# P12_CAN_FD1_4.net
KiCad netlist of a schematic drawn in Altium Designer
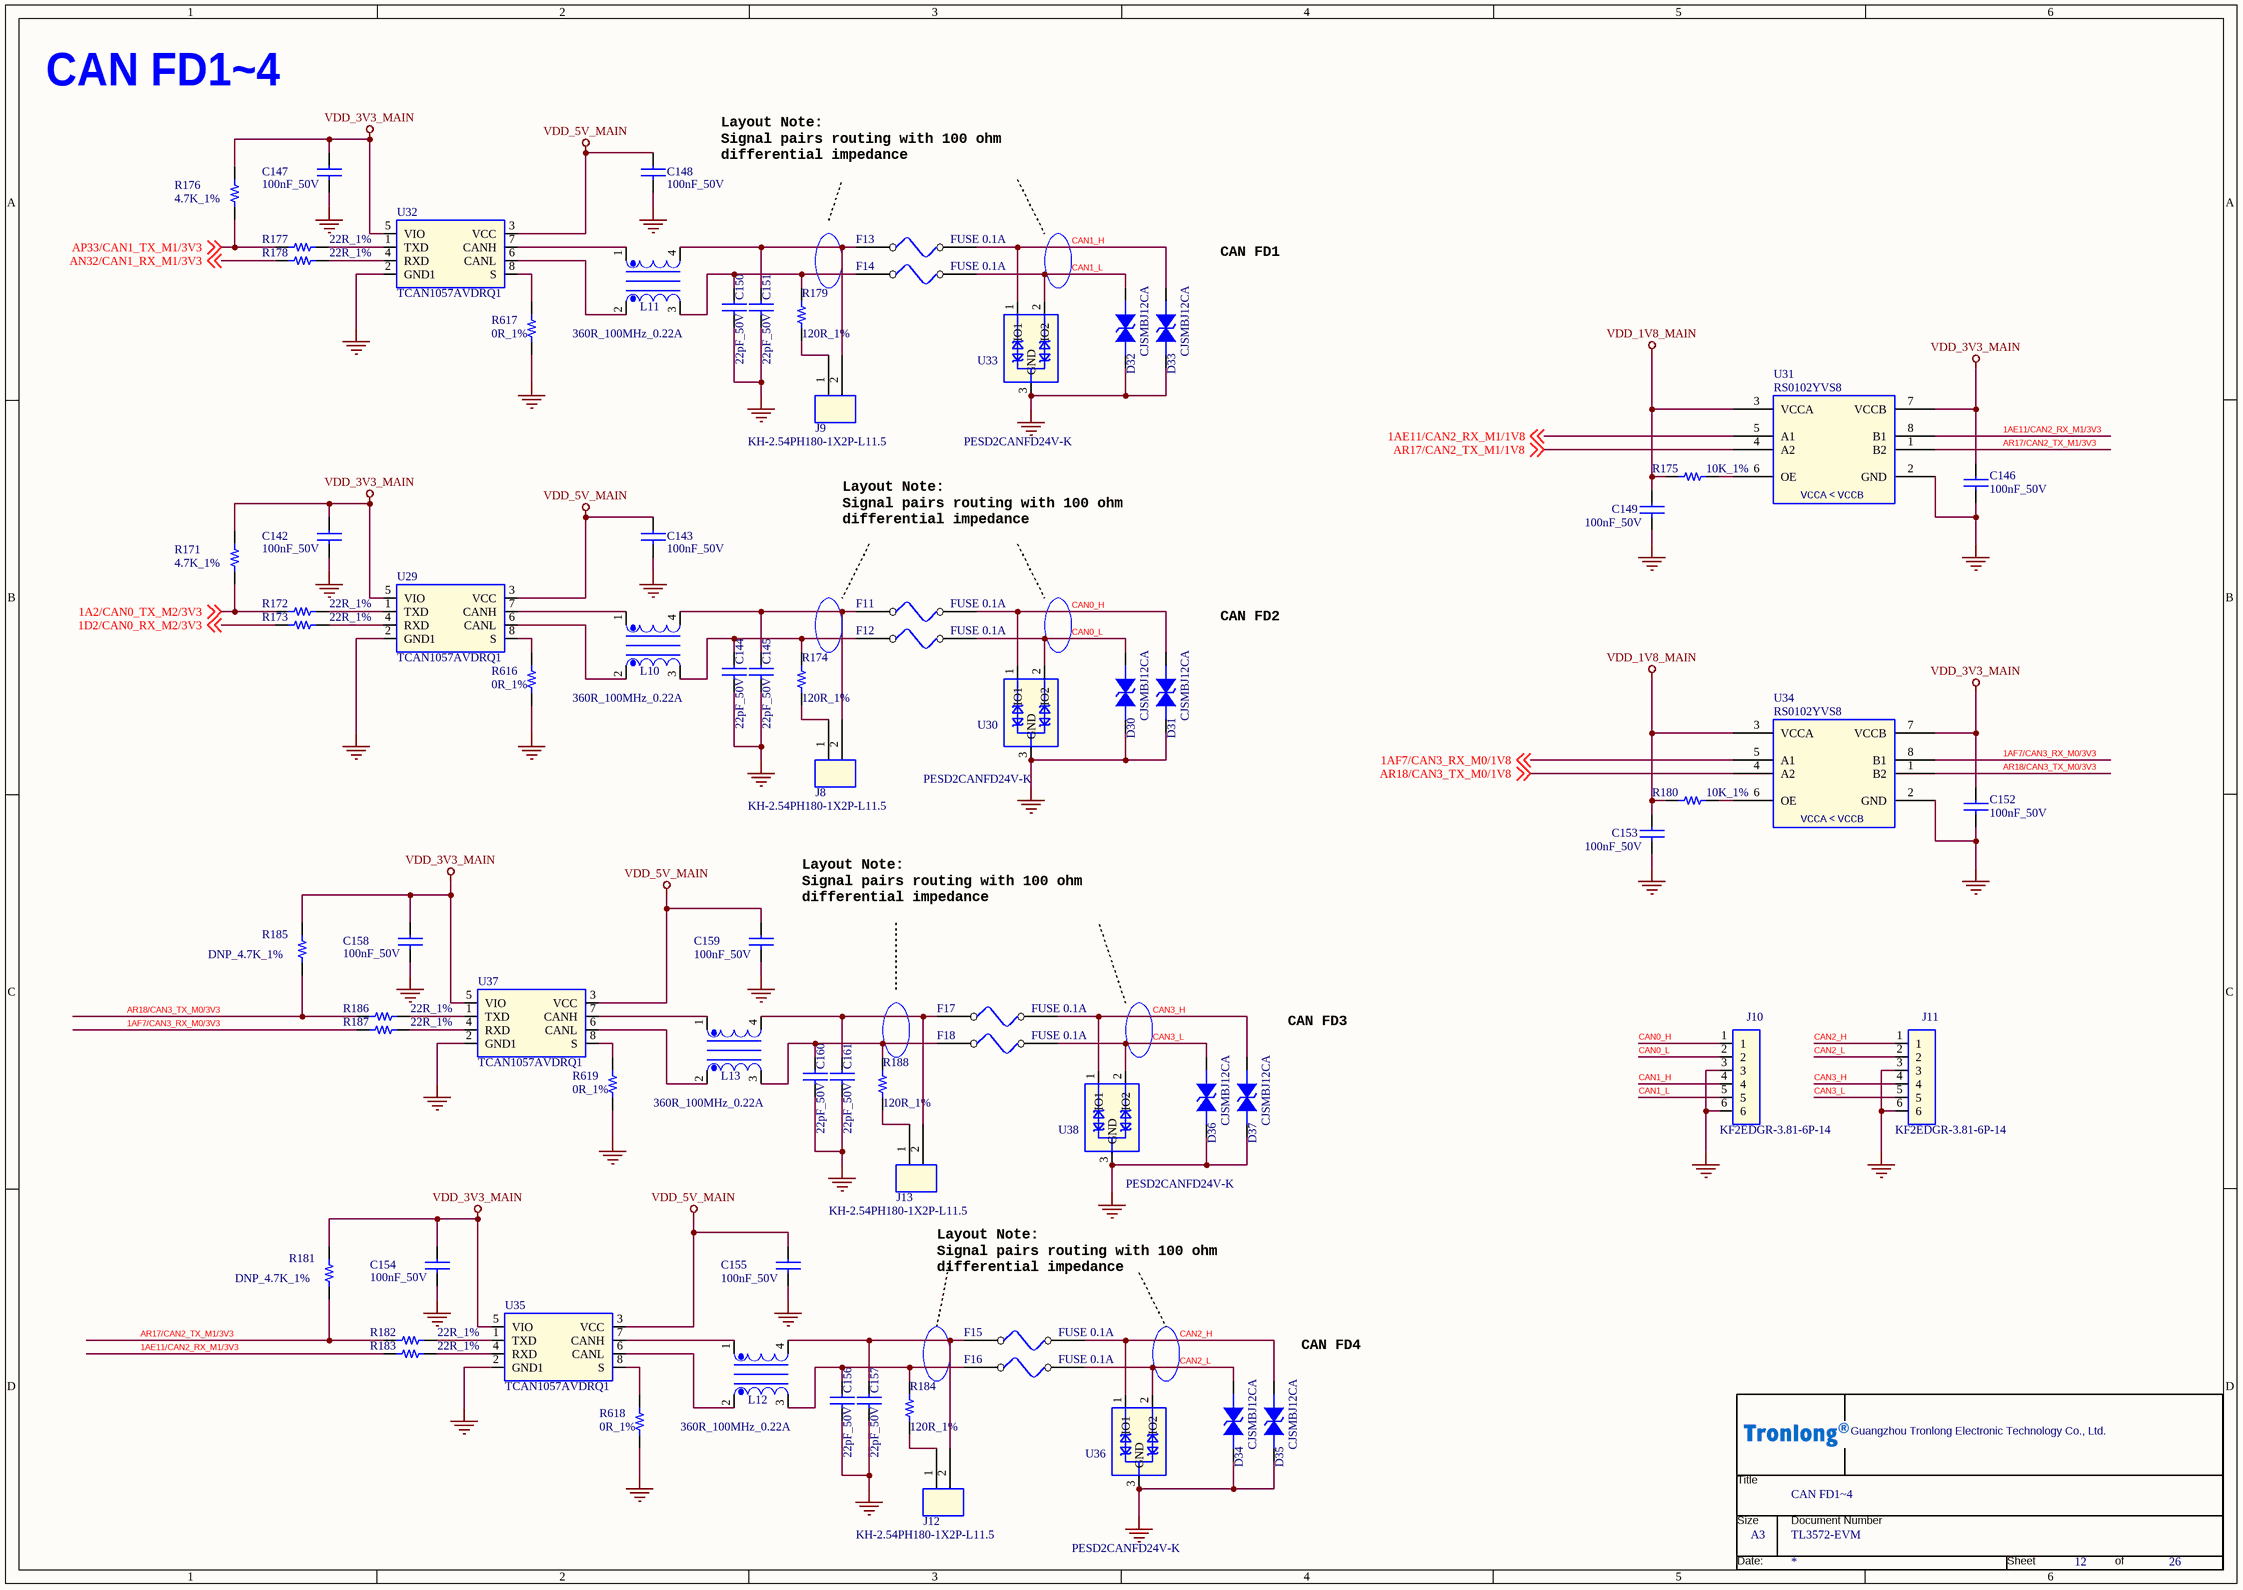
[diagram p0: P12_CAN FD1~4.SchDoc]

(export (version "E")
  (design (tool "Eeschema 10.0.6"))
  (components
    (comp (ref "*")
      (value "Tronlong_TITTLE_20211115")
      (fields
        (field (name "DOC") "TL3572-EVM")
        (field (name "TITLE") "CAN FD1~4")
        (field (name "ORGNAME") "Guangzhou Tronlong Electronic Technology Co., Ltd.")
        (field (name "PAGE SIZE") "A3")
        (field (name "PAGE NUMBER") "12")
        (field (name "PAGE COUNT") "26")
      )
      (libsource (lib "*") (part "Tronlong_TITTLE_20211115"))
    )
    (comp (ref "C142")
      (value "100nF_50V")
      (footprint "C0402")
      (description "贴片陶瓷电容,100nF,10%,50V,X7R")
      (fields
        (field (name "MANUFACTURER") "广东风华高新科技股份有限公司（FH）")
        (field (name "MANUFACTURER PARTNUMBER") "0402B104K500NT")
      )
      (libsource (lib "*") (part "CAP NP_Dup2"))
    )
    (comp (ref "C143")
      (value "100nF_50V")
      (footprint "C0402")
      (description "贴片陶瓷电容,100nF,10%,50V,X7R")
      (fields
        (field (name "MANUFACTURER") "广东风华高新科技股份有限公司（FH）")
        (field (name "MANUFACTURER PARTNUMBER") "0402B104K500NT")
      )
      (libsource (lib "*") (part "CAP NP_Dup2"))
    )
    (comp (ref "C144")
      (value "22pF_50V")
      (footprint "C0603")
      (description "贴片陶瓷电容,22pF,5%,50V,COG")
      (fields
        (field (name "MANUFACTURER PARTNUMBER") "0603CG220J500NT")
        (field (name "MANUFACTURER") "广东风华高新科技股份有限公司（FH）")
      )
      (libsource (lib "*") (part "CAP NP_Dup2"))
    )
    (comp (ref "C145")
      (value "22pF_50V")
      (footprint "C0603")
      (description "贴片陶瓷电容,22pF,5%,50V,COG")
      (fields
        (field (name "MANUFACTURER PARTNUMBER") "0603CG220J500NT")
        (field (name "MANUFACTURER") "广东风华高新科技股份有限公司（FH）")
      )
      (libsource (lib "*") (part "CAP NP_Dup2"))
    )
    (comp (ref "C146")
      (value "100nF_50V")
      (footprint "C0402")
      (description "贴片陶瓷电容,100nF,10%,50V,X7R")
      (fields
        (field (name "MANUFACTURER") "广东风华高新科技股份有限公司（FH）")
        (field (name "MANUFACTURER PARTNUMBER") "0402B104K500NT")
      )
      (libsource (lib "*") (part "CAP NP_Dup3"))
    )
    (comp (ref "C147")
      (value "100nF_50V")
      (footprint "C0402")
      (description "贴片陶瓷电容,100nF,10%,50V,X7R")
      (fields
        (field (name "MANUFACTURER PARTNUMBER") "0402B104K500NT")
        (field (name "MANUFACTURER") "广东风华高新科技股份有限公司（FH）")
      )
      (libsource (lib "*") (part "CAP NP_Dup2"))
    )
    (comp (ref "C148")
      (value "100nF_50V")
      (footprint "C0402")
      (description "贴片陶瓷电容,100nF,10%,50V,X7R")
      (fields
        (field (name "MANUFACTURER PARTNUMBER") "0402B104K500NT")
        (field (name "MANUFACTURER") "广东风华高新科技股份有限公司（FH）")
      )
      (libsource (lib "*") (part "CAP NP_Dup2"))
    )
    (comp (ref "C149")
      (value "100nF_50V")
      (footprint "C0402")
      (description "贴片陶瓷电容,100nF,10%,50V,X7R")
      (fields
        (field (name "MANUFACTURER") "广东风华高新科技股份有限公司（FH）")
        (field (name "MANUFACTURER PARTNUMBER") "0402B104K500NT")
      )
      (libsource (lib "*") (part "CAP NP_Dup3"))
    )
    (comp (ref "C150")
      (value "22pF_50V")
      (footprint "C0603")
      (description "贴片陶瓷电容,22pF,5%,50V,COG")
      (fields
        (field (name "MANUFACTURER PARTNUMBER") "0603CG220J500NT")
        (field (name "MANUFACTURER") "广东风华高新科技股份有限公司（FH）")
      )
      (libsource (lib "*") (part "CAP NP_Dup2"))
    )
    (comp (ref "C151")
      (value "22pF_50V")
      (footprint "C0603")
      (description "贴片陶瓷电容,22pF,5%,50V,COG")
      (fields
        (field (name "MANUFACTURER") "广东风华高新科技股份有限公司（FH）")
        (field (name "MANUFACTURER PARTNUMBER") "0603CG220J500NT")
      )
      (libsource (lib "*") (part "CAP NP_Dup2"))
    )
    (comp (ref "C152")
      (value "100nF_50V")
      (footprint "C0402")
      (description "贴片陶瓷电容,100nF,10%,50V,X7R")
      (fields
        (field (name "MANUFACTURER") "广东风华高新科技股份有限公司（FH）")
        (field (name "MANUFACTURER PARTNUMBER") "0402B104K500NT")
      )
      (libsource (lib "*") (part "CAP NP_Dup3"))
    )
    (comp (ref "C153")
      (value "100nF_50V")
      (footprint "C0402")
      (description "贴片陶瓷电容,100nF,10%,50V,X7R")
      (fields
        (field (name "MANUFACTURER") "广东风华高新科技股份有限公司（FH）")
        (field (name "MANUFACTURER PARTNUMBER") "0402B104K500NT")
      )
      (libsource (lib "*") (part "CAP NP_Dup3"))
    )
    (comp (ref "C154")
      (value "100nF_50V")
      (footprint "C0402")
      (description "贴片陶瓷电容,100nF,10%,50V,X7R")
      (fields
        (field (name "MANUFACTURER") "广东风华高新科技股份有限公司（FH）")
        (field (name "MANUFACTURER PARTNUMBER") "0402B104K500NT")
      )
      (libsource (lib "*") (part "CAP NP_Dup2"))
    )
    (comp (ref "C155")
      (value "100nF_50V")
      (footprint "C0402")
      (description "贴片陶瓷电容,100nF,10%,50V,X7R")
      (fields
        (field (name "MANUFACTURER") "广东风华高新科技股份有限公司（FH）")
        (field (name "MANUFACTURER PARTNUMBER") "0402B104K500NT")
      )
      (libsource (lib "*") (part "CAP NP_Dup2"))
    )
    (comp (ref "C156")
      (value "22pF_50V")
      (footprint "C0603")
      (description "贴片陶瓷电容,22pF,5%,50V,COG")
      (fields
        (field (name "MANUFACTURER PARTNUMBER") "0603CG220J500NT")
        (field (name "MANUFACTURER") "广东风华高新科技股份有限公司（FH）")
      )
      (libsource (lib "*") (part "CAP NP_Dup2"))
    )
    (comp (ref "C157")
      (value "22pF_50V")
      (footprint "C0603")
      (description "贴片陶瓷电容,22pF,5%,50V,COG")
      (fields
        (field (name "MANUFACTURER PARTNUMBER") "0603CG220J500NT")
        (field (name "MANUFACTURER") "广东风华高新科技股份有限公司（FH）")
      )
      (libsource (lib "*") (part "CAP NP_Dup2"))
    )
    (comp (ref "C158")
      (value "100nF_50V")
      (footprint "C0402")
      (description "贴片陶瓷电容,100nF,10%,50V,X7R")
      (fields
        (field (name "MANUFACTURER") "广东风华高新科技股份有限公司（FH）")
        (field (name "MANUFACTURER PARTNUMBER") "0402B104K500NT")
      )
      (libsource (lib "*") (part "CAP NP_Dup2"))
    )
    (comp (ref "C159")
      (value "100nF_50V")
      (footprint "C0402")
      (description "贴片陶瓷电容,100nF,10%,50V,X7R")
      (fields
        (field (name "MANUFACTURER PARTNUMBER") "0402B104K500NT")
        (field (name "MANUFACTURER") "广东风华高新科技股份有限公司（FH）")
      )
      (libsource (lib "*") (part "CAP NP_Dup2"))
    )
    (comp (ref "C160")
      (value "22pF_50V")
      (footprint "C0603")
      (description "贴片陶瓷电容,22pF,5%,50V,COG")
      (fields
        (field (name "MANUFACTURER") "广东风华高新科技股份有限公司（FH）")
        (field (name "MANUFACTURER PARTNUMBER") "0603CG220J500NT")
      )
      (libsource (lib "*") (part "CAP NP_Dup2"))
    )
    (comp (ref "C161")
      (value "22pF_50V")
      (footprint "C0603")
      (description "贴片陶瓷电容,22pF,5%,50V,COG")
      (fields
        (field (name "MANUFACTURER") "广东风华高新科技股份有限公司（FH）")
        (field (name "MANUFACTURER PARTNUMBER") "0603CG220J500NT")
      )
      (libsource (lib "*") (part "CAP NP_Dup2"))
    )
    (comp (ref "D30")
      (value "CJSMBJ12CA")
      (footprint "SMB")
      (description "TVS二极管,VRWM=12V,VBR=13.35V,一组,双向")
      (fields (field (name "MANUFACTURER") "江苏长晶科技股份有限公司（JSCJ）"))
      (libsource (lib "*") (part "DIODE-TRIG"))
    )
    (comp (ref "D31")
      (value "CJSMBJ12CA")
      (footprint "SMB")
      (description "TVS二极管,VRWM=12V,VBR=13.35V,一组,双向")
      (fields (field (name "MANUFACTURER") "江苏长晶科技股份有限公司（JSCJ）"))
      (libsource (lib "*") (part "DIODE-TRIG"))
    )
    (comp (ref "D32")
      (value "CJSMBJ12CA")
      (footprint "SMB")
      (description "TVS二极管,VRWM=12V,VBR=13.35V,一组,双向")
      (fields (field (name "MANUFACTURER") "江苏长晶科技股份有限公司（JSCJ）"))
      (libsource (lib "*") (part "DIODE-TRIG"))
    )
    (comp (ref "D33")
      (value "CJSMBJ12CA")
      (footprint "SMB")
      (description "TVS二极管,VRWM=12V,VBR=13.35V,一组,双向")
      (fields (field (name "MANUFACTURER") "江苏长晶科技股份有限公司（JSCJ）"))
      (libsource (lib "*") (part "DIODE-TRIG"))
    )
    (comp (ref "D34")
      (value "CJSMBJ12CA")
      (footprint "SMB")
      (description "TVS二极管,VRWM=12V,VBR=13.35V,一组,双向")
      (fields (field (name "MANUFACTURER") "江苏长晶科技股份有限公司（JSCJ）"))
      (libsource (lib "*") (part "DIODE-TRIG"))
    )
    (comp (ref "D35")
      (value "CJSMBJ12CA")
      (footprint "SMB")
      (description "TVS二极管,VRWM=12V,VBR=13.35V,一组,双向")
      (fields (field (name "MANUFACTURER") "江苏长晶科技股份有限公司（JSCJ）"))
      (libsource (lib "*") (part "DIODE-TRIG"))
    )
    (comp (ref "D36")
      (value "CJSMBJ12CA")
      (footprint "SMB")
      (description "TVS二极管,VRWM=12V,VBR=13.35V,一组,双向")
      (fields (field (name "MANUFACTURER") "江苏长晶科技股份有限公司（JSCJ）"))
      (libsource (lib "*") (part "DIODE-TRIG"))
    )
    (comp (ref "D37")
      (value "CJSMBJ12CA")
      (footprint "SMB")
      (description "TVS二极管,VRWM=12V,VBR=13.35V,一组,双向")
      (fields (field (name "MANUFACTURER") "江苏长晶科技股份有限公司（JSCJ）"))
      (libsource (lib "*") (part "DIODE-TRIG"))
    )
    (comp (ref "F11")
      (value "FUSE 0.1A")
      (footprint "F0805")
      (description "自恢复保险丝,Vmax=24V,Imax=100A,Ihold=0.1A")
      (fields
        (field (name "MANUFACTURER") "东莞市竞沃电子科技有限公司（TLC）")
        (field (name "MANUFACTURER PARTNUMBER") "TLC-PSMD010/24")
      )
      (libsource (lib "*") (part "FUSE"))
    )
    (comp (ref "F12")
      (value "FUSE 0.1A")
      (footprint "F0805")
      (description "自恢复保险丝,Vmax=24V,Imax=100A,Ihold=0.1A")
      (fields
        (field (name "MANUFACTURER PARTNUMBER") "TLC-PSMD010/24")
        (field (name "MANUFACTURER") "东莞市竞沃电子科技有限公司（TLC）")
      )
      (libsource (lib "*") (part "FUSE"))
    )
    (comp (ref "F13")
      (value "FUSE 0.1A")
      (footprint "F0805")
      (description "自恢复保险丝,Vmax=24V,Imax=100A,Ihold=0.1A")
      (fields
        (field (name "MANUFACTURER") "东莞市竞沃电子科技有限公司（TLC）")
        (field (name "MANUFACTURER PARTNUMBER") "TLC-PSMD010/24")
      )
      (libsource (lib "*") (part "FUSE"))
    )
    (comp (ref "F14")
      (value "FUSE 0.1A")
      (footprint "F0805")
      (description "自恢复保险丝,Vmax=24V,Imax=100A,Ihold=0.1A")
      (fields
        (field (name "MANUFACTURER PARTNUMBER") "TLC-PSMD010/24")
        (field (name "MANUFACTURER") "东莞市竞沃电子科技有限公司（TLC）")
      )
      (libsource (lib "*") (part "FUSE"))
    )
    (comp (ref "F15")
      (value "FUSE 0.1A")
      (footprint "F0805")
      (description "自恢复保险丝,Vmax=24V,Imax=100A,Ihold=0.1A")
      (fields
        (field (name "MANUFACTURER") "东莞市竞沃电子科技有限公司（TLC）")
        (field (name "MANUFACTURER PARTNUMBER") "TLC-PSMD010/24")
      )
      (libsource (lib "*") (part "FUSE"))
    )
    (comp (ref "F16")
      (value "FUSE 0.1A")
      (footprint "F0805")
      (description "自恢复保险丝,Vmax=24V,Imax=100A,Ihold=0.1A")
      (fields
        (field (name "MANUFACTURER PARTNUMBER") "TLC-PSMD010/24")
        (field (name "MANUFACTURER") "东莞市竞沃电子科技有限公司（TLC）")
      )
      (libsource (lib "*") (part "FUSE"))
    )
    (comp (ref "F17")
      (value "FUSE 0.1A")
      (footprint "F0805")
      (description "自恢复保险丝,Vmax=24V,Imax=100A,Ihold=0.1A")
      (fields
        (field (name "MANUFACTURER PARTNUMBER") "TLC-PSMD010/24")
        (field (name "MANUFACTURER") "东莞市竞沃电子科技有限公司（TLC）")
      )
      (libsource (lib "*") (part "FUSE"))
    )
    (comp (ref "F18")
      (value "FUSE 0.1A")
      (footprint "F0805")
      (description "自恢复保险丝,Vmax=24V,Imax=100A,Ihold=0.1A")
      (fields
        (field (name "MANUFACTURER") "东莞市竞沃电子科技有限公司（TLC）")
        (field (name "MANUFACTURER PARTNUMBER") "TLC-PSMD010/24")
      )
      (libsource (lib "*") (part "FUSE"))
    )
    (comp (ref "J8")
      (value "KH-2.54PH180-1X2P-L11.5")
      (footprint "header_1x2p_2d54_male")
      (description "插件单排排针,1x2P,2.54mm,180度")
      (fields (field (name "MANUFACTURER") "深圳市金航标电子有限公司(kinghelm)"))
      (libsource (lib "*") (part "CON2_0"))
    )
    (comp (ref "J9")
      (value "KH-2.54PH180-1X2P-L11.5")
      (footprint "header_1x2p_2d54_male")
      (description "插件单排排针,1x2P,2.54mm,180度")
      (fields (field (name "MANUFACTURER") "深圳市金航标电子有限公司(kinghelm)"))
      (libsource (lib "*") (part "CON2_0"))
    )
    (comp (ref "J10")
      (value "KF2EDGR-3.81-6P-14")
      (footprint "kf2eg_3_81-6p")
      (description "插拔式端子座,1x6P,3.81mm,90度")
      (fields (field (name "MANUFACTURER") "慈溪市科发电子有限公司（KEFA）"))
      (libsource (lib "*") (part "CON6"))
    )
    (comp (ref "J11")
      (value "KF2EDGR-3.81-6P-14")
      (footprint "kf2eg_3_81-6p")
      (description "插拔式端子座,1x6P,3.81mm,90度")
      (fields (field (name "MANUFACTURER") "慈溪市科发电子有限公司（KEFA）"))
      (libsource (lib "*") (part "CON6"))
    )
    (comp (ref "J12")
      (value "KH-2.54PH180-1X2P-L11.5")
      (footprint "header_1x2p_2d54_male")
      (description "插件单排排针,1x2P,2.54mm,180度")
      (fields (field (name "MANUFACTURER") "深圳市金航标电子有限公司(kinghelm)"))
      (libsource (lib "*") (part "CON2_0"))
    )
    (comp (ref "J13")
      (value "KH-2.54PH180-1X2P-L11.5")
      (footprint "header_1x2p_2d54_male")
      (description "插件单排排针,1x2P,2.54mm,180度")
      (fields (field (name "MANUFACTURER") "深圳市金航标电子有限公司(kinghelm)"))
      (libsource (lib "*") (part "CON2_0"))
    )
    (comp (ref "L10")
      (value "360R_100MHz_0.22A")
      (footprint "SMD-L2012M-4P")
      (description "贴片共模电感,500mΩ,0.22A,50V,360Ω@100MHz")
      (fields
        (field (name "MANUFACTURER PARTNUMBER") "ACM2012-361-2P-T001")
        (field (name "MANUFACTURER") "TDK(日本东电化)")
      )
      (libsource (lib "*") (part "TFR_AXA_A_1"))
    )
    (comp (ref "L11")
      (value "360R_100MHz_0.22A")
      (footprint "SMD-L2012M-4P")
      (description "贴片共模电感,500mΩ,0.22A,50V,360Ω@100MHz")
      (fields
        (field (name "MANUFACTURER PARTNUMBER") "ACM2012-361-2P-T001")
        (field (name "MANUFACTURER") "TDK(日本东电化)")
      )
      (libsource (lib "*") (part "TFR_AXA_A_1"))
    )
    (comp (ref "L12")
      (value "360R_100MHz_0.22A")
      (footprint "SMD-L2012M-4P")
      (description "贴片共模电感,500mΩ,0.22A,50V,360Ω@100MHz")
      (fields
        (field (name "MANUFACTURER PARTNUMBER") "ACM2012-361-2P-T001")
        (field (name "MANUFACTURER") "TDK(日本东电化)")
      )
      (libsource (lib "*") (part "TFR_AXA_A_1"))
    )
    (comp (ref "L13")
      (value "360R_100MHz_0.22A")
      (footprint "SMD-L2012M-4P")
      (description "贴片共模电感,500mΩ,0.22A,50V,360Ω@100MHz")
      (fields
        (field (name "MANUFACTURER") "TDK(日本东电化)")
        (field (name "MANUFACTURER PARTNUMBER") "ACM2012-361-2P-T001")
      )
      (libsource (lib "*") (part "TFR_AXA_A_1"))
    )
    (comp (ref "R171")
      (value "4.7K_1%")
      (footprint "R0402")
      (description "贴片电阻,4.7K,±1%,1/16W")
      (fields
        (field (name "MANUFACTURER") "广东风华高新科技股份有限公司（FH）")
        (field (name "MANUFACTURER PARTNUMBER") "RC-02K4701FT")
      )
      (libsource (lib "*") (part "Resistor_Dup3"))
    )
    (comp (ref "R172")
      (value "22R_1%")
      (footprint "R0402")
      (description "贴片电阻,22R,±1%,1/16W")
      (fields
        (field (name "MANUFACTURER") "广东风华高新科技股份有限公司（FH）")
        (field (name "MANUFACTURER PARTNUMBER") "RC-02K22R0FT")
      )
      (libsource (lib "*") (part "Resistor_Dup3"))
    )
    (comp (ref "R173")
      (value "22R_1%")
      (footprint "R0402")
      (description "贴片电阻,22R,±1%,1/16W")
      (fields
        (field (name "MANUFACTURER PARTNUMBER") "RC-02K22R0FT")
        (field (name "MANUFACTURER") "广东风华高新科技股份有限公司（FH）")
      )
      (libsource (lib "*") (part "Resistor_Dup3"))
    )
    (comp (ref "R174")
      (value "120R_1%")
      (footprint "R0805")
      (description "贴片电阻,120R,±1%,1/8W")
      (fields
        (field (name "MANUFACTURER PARTNUMBER") "RS-05K1200FT")
        (field (name "MANUFACTURER") "广东风华高新科技股份有限公司（FH）")
      )
      (libsource (lib "*") (part "Resistor_Dup3"))
    )
    (comp (ref "R175")
      (value "10K_1%")
      (footprint "R0402")
      (description "贴片电阻,10K,±1%,1/16W")
      (fields
        (field (name "MANUFACTURER") "广东风华高新科技股份有限公司（FH）")
        (field (name "MANUFACTURER PARTNUMBER") "RC-02K1002FT")
      )
      (libsource (lib "*") (part "Resistor_Dup4"))
    )
    (comp (ref "R176")
      (value "4.7K_1%")
      (footprint "R0402")
      (description "贴片电阻,4.7K,±1%,1/16W")
      (fields
        (field (name "MANUFACTURER") "广东风华高新科技股份有限公司（FH）")
        (field (name "MANUFACTURER PARTNUMBER") "RC-02K4701FT")
      )
      (libsource (lib "*") (part "Resistor_Dup3"))
    )
    (comp (ref "R177")
      (value "22R_1%")
      (footprint "R0402")
      (description "贴片电阻,22R,±1%,1/16W")
      (fields
        (field (name "MANUFACTURER PARTNUMBER") "RC-02K22R0FT")
        (field (name "MANUFACTURER") "广东风华高新科技股份有限公司（FH）")
      )
      (libsource (lib "*") (part "Resistor_Dup3"))
    )
    (comp (ref "R178")
      (value "22R_1%")
      (footprint "R0402")
      (description "贴片电阻,22R,±1%,1/16W")
      (fields
        (field (name "MANUFACTURER") "广东风华高新科技股份有限公司（FH）")
        (field (name "MANUFACTURER PARTNUMBER") "RC-02K22R0FT")
      )
      (libsource (lib "*") (part "Resistor_Dup3"))
    )
    (comp (ref "R179")
      (value "120R_1%")
      (footprint "R0805")
      (description "贴片电阻,120R,±1%,1/8W")
      (fields
        (field (name "MANUFACTURER PARTNUMBER") "RS-05K1200FT")
        (field (name "MANUFACTURER") "广东风华高新科技股份有限公司（FH）")
      )
      (libsource (lib "*") (part "Resistor_Dup3"))
    )
    (comp (ref "R180")
      (value "10K_1%")
      (footprint "R0402")
      (description "贴片电阻,10K,±1%,1/16W")
      (fields
        (field (name "MANUFACTURER") "广东风华高新科技股份有限公司（FH）")
        (field (name "MANUFACTURER PARTNUMBER") "RC-02K1002FT")
      )
      (libsource (lib "*") (part "Resistor_Dup4"))
    )
    (comp (ref "R181")
      (value "DNP_4.7K_1%")
      (footprint "R0402")
      (description "RC0402FR-074K7L,0402WGF4701TCE")
      (fields
        (field (name "MANUFACTURER PARTNUMBER") "4.7K,±1%,R0402,≥1/16W")
        (field (name "MANUFACTURER") "广州创龙")
      )
      (libsource (lib "*") (part "Resistor_Dup3"))
    )
    (comp (ref "R182")
      (value "22R_1%")
      (footprint "R0402")
      (description "贴片电阻,22R,±1%,1/16W")
      (fields
        (field (name "MANUFACTURER PARTNUMBER") "RC-02K22R0FT")
        (field (name "MANUFACTURER") "广东风华高新科技股份有限公司（FH）")
      )
      (libsource (lib "*") (part "Resistor_Dup3"))
    )
    (comp (ref "R183")
      (value "22R_1%")
      (footprint "R0402")
      (description "贴片电阻,22R,±1%,1/16W")
      (fields
        (field (name "MANUFACTURER") "广东风华高新科技股份有限公司（FH）")
        (field (name "MANUFACTURER PARTNUMBER") "RC-02K22R0FT")
      )
      (libsource (lib "*") (part "Resistor_Dup3"))
    )
    (comp (ref "R184")
      (value "120R_1%")
      (footprint "R0805")
      (description "贴片电阻,120R,±1%,1/8W")
      (fields
        (field (name "MANUFACTURER PARTNUMBER") "RS-05K1200FT")
        (field (name "MANUFACTURER") "广东风华高新科技股份有限公司（FH）")
      )
      (libsource (lib "*") (part "Resistor_Dup3"))
    )
    (comp (ref "R185")
      (value "DNP_4.7K_1%")
      (footprint "R0402")
      (description "RC0402FR-074K7L,0402WGF4701TCE")
      (fields
        (field (name "MANUFACTURER PARTNUMBER") "4.7K,±1%,R0402,≥1/16W")
        (field (name "MANUFACTURER") "广州创龙")
      )
      (libsource (lib "*") (part "Resistor_Dup3"))
    )
    (comp (ref "R186")
      (value "22R_1%")
      (footprint "R0402")
      (description "贴片电阻,22R,±1%,1/16W")
      (fields
        (field (name "MANUFACTURER") "广东风华高新科技股份有限公司（FH）")
        (field (name "MANUFACTURER PARTNUMBER") "RC-02K22R0FT")
      )
      (libsource (lib "*") (part "Resistor_Dup3"))
    )
    (comp (ref "R187")
      (value "22R_1%")
      (footprint "R0402")
      (description "贴片电阻,22R,±1%,1/16W")
      (fields
        (field (name "MANUFACTURER PARTNUMBER") "RC-02K22R0FT")
        (field (name "MANUFACTURER") "广东风华高新科技股份有限公司（FH）")
      )
      (libsource (lib "*") (part "Resistor_Dup3"))
    )
    (comp (ref "R188")
      (value "120R_1%")
      (footprint "R0805")
      (description "贴片电阻,120R,±1%,1/8W")
      (fields
        (field (name "MANUFACTURER") "广东风华高新科技股份有限公司（FH）")
        (field (name "MANUFACTURER PARTNUMBER") "RS-05K1200FT")
      )
      (libsource (lib "*") (part "Resistor_Dup3"))
    )
    (comp (ref "R616")
      (value "0R_1%")
      (footprint "R0402")
      (description "贴片电阻,0R,±1%,1/16W")
      (fields
        (field (name "MANUFACTURER") "广东风华高新科技股份有限公司（FH）")
        (field (name "MANUFACTURER PARTNUMBER") "RC-02000FT")
      )
      (libsource (lib "*") (part "Resistor_Dup3"))
    )
    (comp (ref "R617")
      (value "0R_1%")
      (footprint "R0402")
      (description "贴片电阻,0R,±1%,1/16W")
      (fields
        (field (name "MANUFACTURER") "广东风华高新科技股份有限公司（FH）")
        (field (name "MANUFACTURER PARTNUMBER") "RC-02000FT")
      )
      (libsource (lib "*") (part "Resistor_Dup3"))
    )
    (comp (ref "R618")
      (value "0R_1%")
      (footprint "R0402")
      (description "贴片电阻,0R,±1%,1/16W")
      (fields
        (field (name "MANUFACTURER") "广东风华高新科技股份有限公司（FH）")
        (field (name "MANUFACTURER PARTNUMBER") "RC-02000FT")
      )
      (libsource (lib "*") (part "Resistor_Dup3"))
    )
    (comp (ref "R619")
      (value "0R_1%")
      (footprint "R0402")
      (description "贴片电阻,0R,±1%,1/16W")
      (fields
        (field (name "MANUFACTURER") "广东风华高新科技股份有限公司（FH）")
        (field (name "MANUFACTURER PARTNUMBER") "RC-02000FT")
      )
      (libsource (lib "*") (part "Resistor_Dup3"))
    )
    (comp (ref "U29")
      (value "TCAN1057AVDRQ1")
      (footprint "soic8_d8")
      (description "CAN收发器,非隔离,8Mbps")
      (fields (field (name "MANUFACTURER") "Texas Instruments(美国德州仪器)"))
      (libsource (lib "*") (part "ISO1042_3"))
    )
    (comp (ref "U30")
      (value "PESD2CANFD24V-K")
      (footprint "SOT23-3")
      (description "TVS二极管,VRWM=24V,VBR=26.7V,两组,双向,30KV,30KV")
      (fields (field (name "MANUFACTURER") "派克微电子（深圳）有限公司(pakermicro)"))
      (libsource (lib "*") (part "PSM712"))
    )
    (comp (ref "U31")
      (value "RS0102YVS8")
      (footprint "SOP8-20-91")
      (description "2位双向电平转换器")
      (fields (field (name "MANUFACTURER") "江苏润石科技有限公司（RUNIC）"))
      (libsource (lib "*") (part "TXS0102DCUR_0"))
    )
    (comp (ref "U32")
      (value "TCAN1057AVDRQ1")
      (footprint "soic8_d8")
      (description "CAN收发器,非隔离,8Mbps")
      (fields (field (name "MANUFACTURER") "Texas Instruments(美国德州仪器)"))
      (libsource (lib "*") (part "ISO1042_3"))
    )
    (comp (ref "U33")
      (value "PESD2CANFD24V-K")
      (footprint "SOT23-3")
      (description "TVS二极管,VRWM=24V,VBR=26.7V,两组,双向,30KV,30KV")
      (fields (field (name "MANUFACTURER") "派克微电子（深圳）有限公司(pakermicro)"))
      (libsource (lib "*") (part "PSM712"))
    )
    (comp (ref "U34")
      (value "RS0102YVS8")
      (footprint "SOP8-20-91")
      (description "2位双向电平转换器")
      (fields (field (name "MANUFACTURER") "江苏润石科技有限公司（RUNIC）"))
      (libsource (lib "*") (part "TXS0102DCUR_0"))
    )
    (comp (ref "U35")
      (value "TCAN1057AVDRQ1")
      (footprint "soic8_d8")
      (description "CAN收发器,非隔离,8Mbps")
      (fields (field (name "MANUFACTURER") "Texas Instruments(美国德州仪器)"))
      (libsource (lib "*") (part "ISO1042_3"))
    )
    (comp (ref "U36")
      (value "PESD2CANFD24V-K")
      (footprint "SOT23-3")
      (description "TVS二极管,VRWM=24V,VBR=26.7V,两组,双向,30KV,30KV")
      (fields (field (name "MANUFACTURER") "派克微电子（深圳）有限公司(pakermicro)"))
      (libsource (lib "*") (part "PSM712"))
    )
    (comp (ref "U37")
      (value "TCAN1057AVDRQ1")
      (footprint "soic8_d8")
      (description "CAN收发器,非隔离,8Mbps")
      (fields (field (name "MANUFACTURER") "Texas Instruments(美国德州仪器)"))
      (libsource (lib "*") (part "ISO1042_3"))
    )
    (comp (ref "U38")
      (value "PESD2CANFD24V-K")
      (footprint "SOT23-3")
      (description "TVS二极管,VRWM=24V,VBR=26.7V,两组,双向,30KV,30KV")
      (fields (field (name "MANUFACTURER") "派克微电子（深圳）有限公司(pakermicro)"))
      (libsource (lib "*") (part "PSM712"))
    )
  )
  (nets
    (net (code "1") (name "/1AE11{slash}CAN2_RX_M1{slash}3V3") (class "Default")
      (node (ref "R183") (pin "1") (pinfunction "1_1") (pintype "passive"))
      (node (ref "U31") (pin "8") (pinfunction "B1_8") (pintype "passive"))
    )
    (net (code "2") (name "/1AF7{slash}CAN3_RX_M0{slash}3V3") (class "Default")
      (node (ref "R187") (pin "1") (pinfunction "1_1") (pintype "passive"))
      (node (ref "U34") (pin "8") (pinfunction "B1_8") (pintype "passive"))
    )
    (net (code "3") (name "/AR17{slash}CAN2_TX_M1{slash}3V3") (class "Default")
      (node (ref "R181") (pin "2") (pinfunction "2_2") (pintype "passive"))
      (node (ref "R182") (pin "1") (pinfunction "1_1") (pintype "passive"))
      (node (ref "U31") (pin "1") (pinfunction "B2_1") (pintype "passive"))
    )
    (net (code "4") (name "/AR18{slash}CAN3_TX_M0{slash}3V3") (class "Default")
      (node (ref "R185") (pin "2") (pinfunction "2_2") (pintype "passive"))
      (node (ref "R186") (pin "1") (pinfunction "1_1") (pintype "passive"))
      (node (ref "U34") (pin "1") (pinfunction "B2_1") (pintype "passive"))
    )
    (net (code "5") (name "/CAN0_H") (class "Default")
      (node (ref "D31") (pin "2") (pinfunction "2_2") (pintype "passive"))
      (node (ref "F11") (pin "2") (pinfunction "2_2") (pintype "passive"))
      (node (ref "J10") (pin "1") (pinfunction "1_1") (pintype "passive"))
      (node (ref "U30") (pin "1") (pinfunction "IO1_1") (pintype "passive"))
    )
    (net (code "6") (name "/CAN0_L") (class "Default")
      (node (ref "D30") (pin "2") (pinfunction "2_2") (pintype "passive"))
      (node (ref "F12") (pin "2") (pinfunction "2_2") (pintype "passive"))
      (node (ref "J10") (pin "2") (pinfunction "2_2") (pintype "passive"))
      (node (ref "U30") (pin "2") (pinfunction "IO2_2") (pintype "passive"))
    )
    (net (code "7") (name "/CAN1_H") (class "Default")
      (node (ref "D33") (pin "2") (pinfunction "2_2") (pintype "passive"))
      (node (ref "F13") (pin "2") (pinfunction "2_2") (pintype "passive"))
      (node (ref "J10") (pin "4") (pinfunction "4_4") (pintype "passive"))
      (node (ref "U33") (pin "1") (pinfunction "IO1_1") (pintype "passive"))
    )
    (net (code "8") (name "/CAN1_L") (class "Default")
      (node (ref "D32") (pin "2") (pinfunction "2_2") (pintype "passive"))
      (node (ref "F14") (pin "2") (pinfunction "2_2") (pintype "passive"))
      (node (ref "J10") (pin "5") (pinfunction "5_5") (pintype "passive"))
      (node (ref "U33") (pin "2") (pinfunction "IO2_2") (pintype "passive"))
    )
    (net (code "9") (name "/CAN2_H") (class "Default")
      (node (ref "D35") (pin "2") (pinfunction "2_2") (pintype "passive"))
      (node (ref "F15") (pin "2") (pinfunction "2_2") (pintype "passive"))
      (node (ref "J11") (pin "1") (pinfunction "1_1") (pintype "passive"))
      (node (ref "U36") (pin "1") (pinfunction "IO1_1") (pintype "passive"))
    )
    (net (code "10") (name "/CAN2_L") (class "Default")
      (node (ref "D34") (pin "2") (pinfunction "2_2") (pintype "passive"))
      (node (ref "F16") (pin "2") (pinfunction "2_2") (pintype "passive"))
      (node (ref "J11") (pin "2") (pinfunction "2_2") (pintype "passive"))
      (node (ref "U36") (pin "2") (pinfunction "IO2_2") (pintype "passive"))
    )
    (net (code "11") (name "/CAN3_H") (class "Default")
      (node (ref "D37") (pin "2") (pinfunction "2_2") (pintype "passive"))
      (node (ref "F17") (pin "2") (pinfunction "2_2") (pintype "passive"))
      (node (ref "J11") (pin "4") (pinfunction "4_4") (pintype "passive"))
      (node (ref "U38") (pin "1") (pinfunction "IO1_1") (pintype "passive"))
    )
    (net (code "12") (name "/CAN3_L") (class "Default")
      (node (ref "D36") (pin "2") (pinfunction "2_2") (pintype "passive"))
      (node (ref "F18") (pin "2") (pinfunction "2_2") (pintype "passive"))
      (node (ref "J11") (pin "5") (pinfunction "5_5") (pintype "passive"))
      (node (ref "U38") (pin "2") (pinfunction "IO2_2") (pintype "passive"))
    )
    (net (code "13") (name "1A2{slash}CAN0_TX_M2{slash}3V3") (class "Default")
      (node (ref "R171") (pin "2") (pinfunction "2_2") (pintype "passive"))
      (node (ref "R172") (pin "1") (pinfunction "1_1") (pintype "passive"))
    )
    (net (code "14") (name "1AE11{slash}CAN2_RX_M1{slash}1V8") (class "Default")
      (node (ref "U31") (pin "5") (pinfunction "A1_5") (pintype "passive"))
    )
    (net (code "15") (name "1AF7{slash}CAN3_RX_M0{slash}1V8") (class "Default")
      (node (ref "U34") (pin "5") (pinfunction "A1_5") (pintype "passive"))
    )
    (net (code "16") (name "1D2{slash}CAN0_RX_M2{slash}3V3") (class "Default")
      (node (ref "R173") (pin "1") (pinfunction "1_1") (pintype "passive"))
    )
    (net (code "17") (name "AN32{slash}CAN1_RX_M1{slash}3V3") (class "Default")
      (node (ref "R178") (pin "1") (pinfunction "1_1") (pintype "passive"))
    )
    (net (code "18") (name "AP33{slash}CAN1_TX_M1{slash}3V3") (class "Default")
      (node (ref "R176") (pin "2") (pinfunction "2_2") (pintype "passive"))
      (node (ref "R177") (pin "1") (pinfunction "1_1") (pintype "passive"))
    )
    (net (code "19") (name "AR17{slash}CAN2_TX_M1{slash}1V8") (class "Default")
      (node (ref "U31") (pin "4") (pinfunction "A2_4") (pintype "passive"))
    )
    (net (code "20") (name "AR18{slash}CAN3_TX_M0{slash}1V8") (class "Default")
      (node (ref "U34") (pin "4") (pinfunction "A2_4") (pintype "passive"))
    )
    (net (code "21") (name "GND") (class "Default")
      (node (ref "C142") (pin "2") (pinfunction "2_2") (pintype "passive"))
      (node (ref "C143") (pin "2") (pinfunction "2_2") (pintype "passive"))
      (node (ref "C144") (pin "2") (pinfunction "2_2") (pintype "passive"))
      (node (ref "C145") (pin "2") (pinfunction "2_2") (pintype "passive"))
      (node (ref "C146") (pin "2") (pinfunction "2_2") (pintype "passive"))
      (node (ref "C147") (pin "2") (pinfunction "2_2") (pintype "passive"))
      (node (ref "C148") (pin "2") (pinfunction "2_2") (pintype "passive"))
      (node (ref "C149") (pin "2") (pinfunction "2_2") (pintype "passive"))
      (node (ref "C150") (pin "2") (pinfunction "2_2") (pintype "passive"))
      (node (ref "C151") (pin "2") (pinfunction "2_2") (pintype "passive"))
      (node (ref "C152") (pin "2") (pinfunction "2_2") (pintype "passive"))
      (node (ref "C153") (pin "2") (pinfunction "2_2") (pintype "passive"))
      (node (ref "C154") (pin "2") (pinfunction "2_2") (pintype "passive"))
      (node (ref "C155") (pin "2") (pinfunction "2_2") (pintype "passive"))
      (node (ref "C156") (pin "2") (pinfunction "2_2") (pintype "passive"))
      (node (ref "C157") (pin "2") (pinfunction "2_2") (pintype "passive"))
      (node (ref "C158") (pin "2") (pinfunction "2_2") (pintype "passive"))
      (node (ref "C159") (pin "2") (pinfunction "2_2") (pintype "passive"))
      (node (ref "C160") (pin "2") (pinfunction "2_2") (pintype "passive"))
      (node (ref "C161") (pin "2") (pinfunction "2_2") (pintype "passive"))
      (node (ref "D30") (pin "1") (pinfunction "1_1") (pintype "passive"))
      (node (ref "D31") (pin "1") (pinfunction "1_1") (pintype "passive"))
      (node (ref "D32") (pin "1") (pinfunction "1_1") (pintype "passive"))
      (node (ref "D33") (pin "1") (pinfunction "1_1") (pintype "passive"))
      (node (ref "D34") (pin "1") (pinfunction "1_1") (pintype "passive"))
      (node (ref "D35") (pin "1") (pinfunction "1_1") (pintype "passive"))
      (node (ref "D36") (pin "1") (pinfunction "1_1") (pintype "passive"))
      (node (ref "D37") (pin "1") (pinfunction "1_1") (pintype "passive"))
      (node (ref "J10") (pin "3") (pinfunction "3_3") (pintype "passive"))
      (node (ref "J10") (pin "6") (pinfunction "6_6") (pintype "passive"))
      (node (ref "J11") (pin "3") (pinfunction "3_3") (pintype "passive"))
      (node (ref "J11") (pin "6") (pinfunction "6_6") (pintype "passive"))
      (node (ref "R616") (pin "2") (pinfunction "2_2") (pintype "passive"))
      (node (ref "R617") (pin "2") (pinfunction "2_2") (pintype "passive"))
      (node (ref "R618") (pin "2") (pinfunction "2_2") (pintype "passive"))
      (node (ref "R619") (pin "2") (pinfunction "2_2") (pintype "passive"))
      (node (ref "U29") (pin "2") (pinfunction "GND1_2") (pintype "power_in"))
      (node (ref "U30") (pin "3") (pinfunction "GND_3") (pintype "passive"))
      (node (ref "U31") (pin "2") (pinfunction "GND_2") (pintype "passive"))
      (node (ref "U32") (pin "2") (pinfunction "GND1_2") (pintype "power_in"))
      (node (ref "U33") (pin "3") (pinfunction "GND_3") (pintype "passive"))
      (node (ref "U34") (pin "2") (pinfunction "GND_2") (pintype "passive"))
      (node (ref "U35") (pin "2") (pinfunction "GND1_2") (pintype "power_in"))
      (node (ref "U36") (pin "3") (pinfunction "GND_3") (pintype "passive"))
      (node (ref "U37") (pin "2") (pinfunction "GND1_2") (pintype "power_in"))
      (node (ref "U38") (pin "3") (pinfunction "GND_3") (pintype "passive"))
    )
    (net (code "22") (name "Net-(C144-Pad1)") (class "Default")
      (node (ref "C144") (pin "1") (pinfunction "1_1") (pintype "passive"))
      (node (ref "F12") (pin "1") (pinfunction "1_1") (pintype "passive"))
      (node (ref "L10") (pin "3") (pinfunction "3_3") (pintype "passive"))
      (node (ref "R174") (pin "2") (pinfunction "2_2") (pintype "passive"))
    )
    (net (code "23") (name "Net-(C145-Pad1)") (class "Default")
      (node (ref "C145") (pin "1") (pinfunction "1_1") (pintype "passive"))
      (node (ref "F11") (pin "1") (pinfunction "1_1") (pintype "passive"))
      (node (ref "J8") (pin "2") (pinfunction "2_2") (pintype "passive"))
      (node (ref "L10") (pin "4") (pinfunction "4_4") (pintype "passive"))
    )
    (net (code "24") (name "Net-(C150-Pad1)") (class "Default")
      (node (ref "C150") (pin "1") (pinfunction "1_1") (pintype "passive"))
      (node (ref "F14") (pin "1") (pinfunction "1_1") (pintype "passive"))
      (node (ref "L11") (pin "3") (pinfunction "3_3") (pintype "passive"))
      (node (ref "R179") (pin "2") (pinfunction "2_2") (pintype "passive"))
    )
    (net (code "25") (name "Net-(C151-Pad1)") (class "Default")
      (node (ref "C151") (pin "1") (pinfunction "1_1") (pintype "passive"))
      (node (ref "F13") (pin "1") (pinfunction "1_1") (pintype "passive"))
      (node (ref "J9") (pin "2") (pinfunction "2_2") (pintype "passive"))
      (node (ref "L11") (pin "4") (pinfunction "4_4") (pintype "passive"))
    )
    (net (code "26") (name "Net-(C156-Pad1)") (class "Default")
      (node (ref "C156") (pin "1") (pinfunction "1_1") (pintype "passive"))
      (node (ref "F16") (pin "1") (pinfunction "1_1") (pintype "passive"))
      (node (ref "L12") (pin "3") (pinfunction "3_3") (pintype "passive"))
      (node (ref "R184") (pin "2") (pinfunction "2_2") (pintype "passive"))
    )
    (net (code "27") (name "Net-(C157-Pad1)") (class "Default")
      (node (ref "C157") (pin "1") (pinfunction "1_1") (pintype "passive"))
      (node (ref "F15") (pin "1") (pinfunction "1_1") (pintype "passive"))
      (node (ref "J12") (pin "2") (pinfunction "2_2") (pintype "passive"))
      (node (ref "L12") (pin "4") (pinfunction "4_4") (pintype "passive"))
    )
    (net (code "28") (name "Net-(C160-Pad1)") (class "Default")
      (node (ref "C160") (pin "1") (pinfunction "1_1") (pintype "passive"))
      (node (ref "F18") (pin "1") (pinfunction "1_1") (pintype "passive"))
      (node (ref "L13") (pin "3") (pinfunction "3_3") (pintype "passive"))
      (node (ref "R188") (pin "2") (pinfunction "2_2") (pintype "passive"))
    )
    (net (code "29") (name "Net-(C161-Pad1)") (class "Default")
      (node (ref "C161") (pin "1") (pinfunction "1_1") (pintype "passive"))
      (node (ref "F17") (pin "1") (pinfunction "1_1") (pintype "passive"))
      (node (ref "J13") (pin "2") (pinfunction "2_2") (pintype "passive"))
      (node (ref "L13") (pin "4") (pinfunction "4_4") (pintype "passive"))
    )
    (net (code "30") (name "Net-(J8-Pad1)") (class "Default")
      (node (ref "J8") (pin "1") (pinfunction "1_1") (pintype "passive"))
      (node (ref "R174") (pin "1") (pinfunction "1_1") (pintype "passive"))
    )
    (net (code "31") (name "Net-(J9-Pad1)") (class "Default")
      (node (ref "J9") (pin "1") (pinfunction "1_1") (pintype "passive"))
      (node (ref "R179") (pin "1") (pinfunction "1_1") (pintype "passive"))
    )
    (net (code "32") (name "Net-(J12-Pad1)") (class "Default")
      (node (ref "J12") (pin "1") (pinfunction "1_1") (pintype "passive"))
      (node (ref "R184") (pin "1") (pinfunction "1_1") (pintype "passive"))
    )
    (net (code "33") (name "Net-(J13-Pad1)") (class "Default")
      (node (ref "J13") (pin "1") (pinfunction "1_1") (pintype "passive"))
      (node (ref "R188") (pin "1") (pinfunction "1_1") (pintype "passive"))
    )
    (net (code "34") (name "Net-(U29-CANH)") (class "Default")
      (node (ref "L10") (pin "1") (pinfunction "1_1") (pintype "passive"))
      (node (ref "U29") (pin "7") (pinfunction "CANH_7") (pintype "passive"))
    )
    (net (code "35") (name "Net-(U29-CANL)") (class "Default")
      (node (ref "L10") (pin "2") (pinfunction "2_2") (pintype "passive"))
      (node (ref "U29") (pin "6") (pinfunction "CANL_6") (pintype "passive"))
    )
    (net (code "36") (name "Net-(U29-RXD)") (class "Default")
      (node (ref "R173") (pin "2") (pinfunction "2_2") (pintype "passive"))
      (node (ref "U29") (pin "4") (pinfunction "RXD_4") (pintype "passive"))
    )
    (net (code "37") (name "Net-(U29-S)") (class "Default")
      (node (ref "R616") (pin "1") (pinfunction "1_1") (pintype "passive"))
      (node (ref "U29") (pin "8") (pinfunction "S_8") (pintype "power_in"))
    )
    (net (code "38") (name "Net-(U29-TXD)") (class "Default")
      (node (ref "R172") (pin "2") (pinfunction "2_2") (pintype "passive"))
      (node (ref "U29") (pin "1") (pinfunction "TXD_1") (pintype "passive"))
    )
    (net (code "39") (name "Net-(U31-OE)") (class "Default")
      (node (ref "R175") (pin "2") (pinfunction "2_2") (pintype "passive"))
      (node (ref "U31") (pin "6") (pinfunction "OE_6") (pintype "passive"))
    )
    (net (code "40") (name "Net-(U32-CANH)") (class "Default")
      (node (ref "L11") (pin "1") (pinfunction "1_1") (pintype "passive"))
      (node (ref "U32") (pin "7") (pinfunction "CANH_7") (pintype "passive"))
    )
    (net (code "41") (name "Net-(U32-CANL)") (class "Default")
      (node (ref "L11") (pin "2") (pinfunction "2_2") (pintype "passive"))
      (node (ref "U32") (pin "6") (pinfunction "CANL_6") (pintype "passive"))
    )
    (net (code "42") (name "Net-(U32-RXD)") (class "Default")
      (node (ref "R178") (pin "2") (pinfunction "2_2") (pintype "passive"))
      (node (ref "U32") (pin "4") (pinfunction "RXD_4") (pintype "passive"))
    )
    (net (code "43") (name "Net-(U32-S)") (class "Default")
      (node (ref "R617") (pin "1") (pinfunction "1_1") (pintype "passive"))
      (node (ref "U32") (pin "8") (pinfunction "S_8") (pintype "power_in"))
    )
    (net (code "44") (name "Net-(U32-TXD)") (class "Default")
      (node (ref "R177") (pin "2") (pinfunction "2_2") (pintype "passive"))
      (node (ref "U32") (pin "1") (pinfunction "TXD_1") (pintype "passive"))
    )
    (net (code "45") (name "Net-(U34-OE)") (class "Default")
      (node (ref "R180") (pin "2") (pinfunction "2_2") (pintype "passive"))
      (node (ref "U34") (pin "6") (pinfunction "OE_6") (pintype "passive"))
    )
    (net (code "46") (name "Net-(U35-CANH)") (class "Default")
      (node (ref "L12") (pin "1") (pinfunction "1_1") (pintype "passive"))
      (node (ref "U35") (pin "7") (pinfunction "CANH_7") (pintype "passive"))
    )
    (net (code "47") (name "Net-(U35-CANL)") (class "Default")
      (node (ref "L12") (pin "2") (pinfunction "2_2") (pintype "passive"))
      (node (ref "U35") (pin "6") (pinfunction "CANL_6") (pintype "passive"))
    )
    (net (code "48") (name "Net-(U35-RXD)") (class "Default")
      (node (ref "R183") (pin "2") (pinfunction "2_2") (pintype "passive"))
      (node (ref "U35") (pin "4") (pinfunction "RXD_4") (pintype "passive"))
    )
    (net (code "49") (name "Net-(U35-S)") (class "Default")
      (node (ref "R618") (pin "1") (pinfunction "1_1") (pintype "passive"))
      (node (ref "U35") (pin "8") (pinfunction "S_8") (pintype "power_in"))
    )
    (net (code "50") (name "Net-(U35-TXD)") (class "Default")
      (node (ref "R182") (pin "2") (pinfunction "2_2") (pintype "passive"))
      (node (ref "U35") (pin "1") (pinfunction "TXD_1") (pintype "passive"))
    )
    (net (code "51") (name "Net-(U37-CANH)") (class "Default")
      (node (ref "L13") (pin "1") (pinfunction "1_1") (pintype "passive"))
      (node (ref "U37") (pin "7") (pinfunction "CANH_7") (pintype "passive"))
    )
    (net (code "52") (name "Net-(U37-CANL)") (class "Default")
      (node (ref "L13") (pin "2") (pinfunction "2_2") (pintype "passive"))
      (node (ref "U37") (pin "6") (pinfunction "CANL_6") (pintype "passive"))
    )
    (net (code "53") (name "Net-(U37-RXD)") (class "Default")
      (node (ref "R187") (pin "2") (pinfunction "2_2") (pintype "passive"))
      (node (ref "U37") (pin "4") (pinfunction "RXD_4") (pintype "passive"))
    )
    (net (code "54") (name "Net-(U37-S)") (class "Default")
      (node (ref "R619") (pin "1") (pinfunction "1_1") (pintype "passive"))
      (node (ref "U37") (pin "8") (pinfunction "S_8") (pintype "power_in"))
    )
    (net (code "55") (name "Net-(U37-TXD)") (class "Default")
      (node (ref "R186") (pin "2") (pinfunction "2_2") (pintype "passive"))
      (node (ref "U37") (pin "1") (pinfunction "TXD_1") (pintype "passive"))
    )
    (net (code "56") (name "VDD_1V8_MAIN") (class "Default")
      (node (ref "C149") (pin "1") (pinfunction "1_1") (pintype "passive"))
      (node (ref "C153") (pin "1") (pinfunction "1_1") (pintype "passive"))
      (node (ref "R175") (pin "1") (pinfunction "1_1") (pintype "passive"))
      (node (ref "R180") (pin "1") (pinfunction "1_1") (pintype "passive"))
      (node (ref "U31") (pin "3") (pinfunction "VCCA_3") (pintype "passive"))
      (node (ref "U34") (pin "3") (pinfunction "VCCA_3") (pintype "passive"))
    )
    (net (code "57") (name "VDD_3V3_MAIN") (class "Default")
      (node (ref "C142") (pin "1") (pinfunction "1_1") (pintype "passive"))
      (node (ref "C146") (pin "1") (pinfunction "1_1") (pintype "passive"))
      (node (ref "C147") (pin "1") (pinfunction "1_1") (pintype "passive"))
      (node (ref "C152") (pin "1") (pinfunction "1_1") (pintype "passive"))
      (node (ref "C154") (pin "1") (pinfunction "1_1") (pintype "passive"))
      (node (ref "C158") (pin "1") (pinfunction "1_1") (pintype "passive"))
      (node (ref "R171") (pin "1") (pinfunction "1_1") (pintype "passive"))
      (node (ref "R176") (pin "1") (pinfunction "1_1") (pintype "passive"))
      (node (ref "R181") (pin "1") (pinfunction "1_1") (pintype "passive"))
      (node (ref "R185") (pin "1") (pinfunction "1_1") (pintype "passive"))
      (node (ref "U29") (pin "5") (pinfunction "VIO_5") (pintype "power_in"))
      (node (ref "U31") (pin "7") (pinfunction "VCCB_7") (pintype "passive"))
      (node (ref "U32") (pin "5") (pinfunction "VIO_5") (pintype "power_in"))
      (node (ref "U34") (pin "7") (pinfunction "VCCB_7") (pintype "passive"))
      (node (ref "U35") (pin "5") (pinfunction "VIO_5") (pintype "power_in"))
      (node (ref "U37") (pin "5") (pinfunction "VIO_5") (pintype "power_in"))
    )
    (net (code "58") (name "VDD_5V_MAIN") (class "Default")
      (node (ref "C143") (pin "1") (pinfunction "1_1") (pintype "passive"))
      (node (ref "C148") (pin "1") (pinfunction "1_1") (pintype "passive"))
      (node (ref "C155") (pin "1") (pinfunction "1_1") (pintype "passive"))
      (node (ref "C159") (pin "1") (pinfunction "1_1") (pintype "passive"))
      (node (ref "U29") (pin "3") (pinfunction "VCC_3") (pintype "power_in"))
      (node (ref "U32") (pin "3") (pinfunction "VCC_3") (pintype "power_in"))
      (node (ref "U35") (pin "3") (pinfunction "VCC_3") (pintype "power_in"))
      (node (ref "U37") (pin "3") (pinfunction "VCC_3") (pintype "power_in"))
    )
  )
)
